# Laser_Control_Board.net
KiCad netlist of a schematic drawn in EAGLE
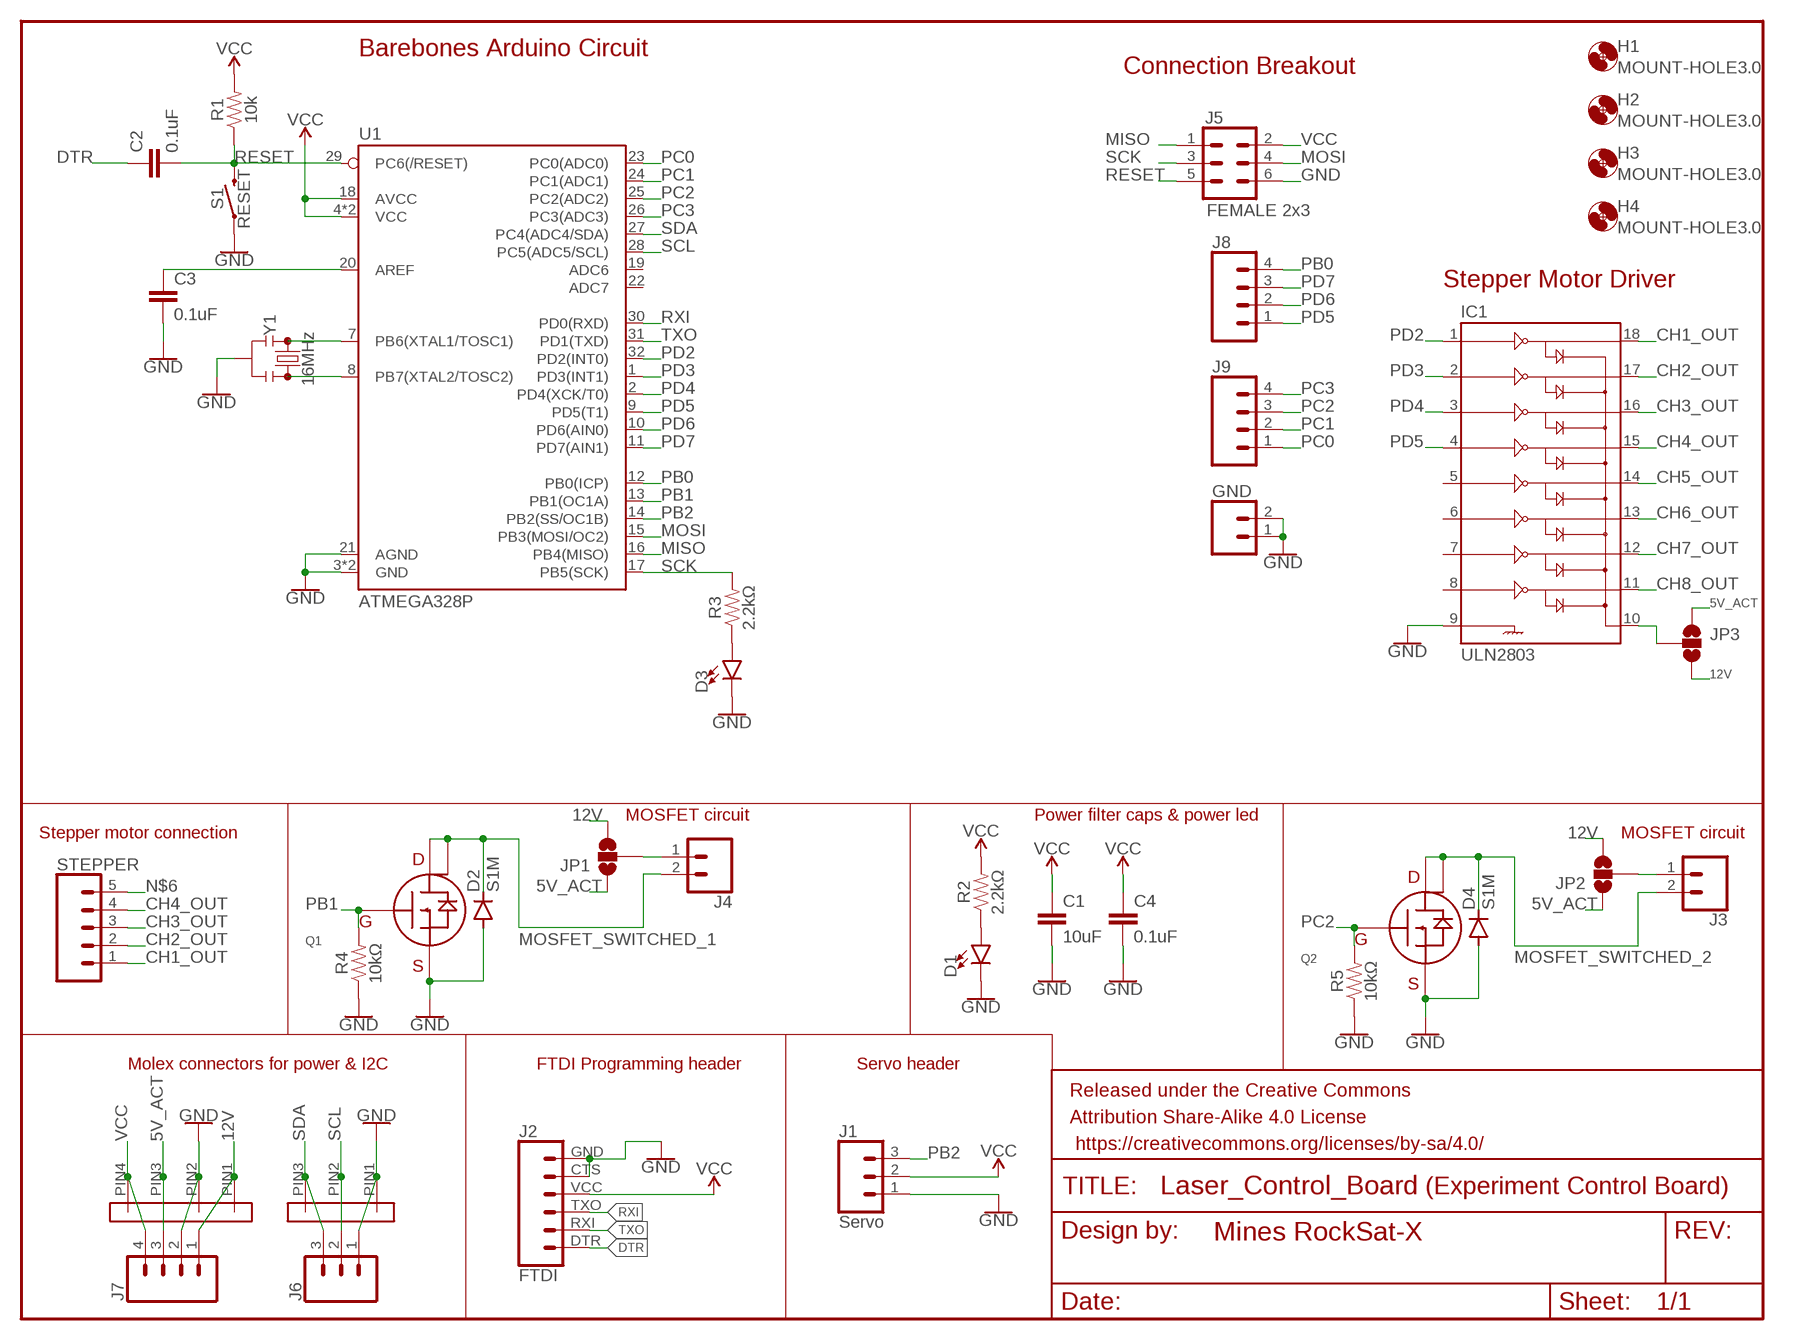
[diagram p0: schematic, sheet 1]

(export (version "E")
  (design (tool "Eeschema 10.0.6"))
  (components
    (comp (ref "C1")
      (value "10uF")
      (footprint "eagle-import:0805")
      (libsource (lib "eagle-import") (part "10UF-0805-10V-10%"))
    )
    (comp (ref "C2")
      (value "0.1uF")
      (footprint "eagle-import:0805")
      (libsource (lib "eagle-import") (part "2.2UF-0805-25V-(+80/-20%)"))
    )
    (comp (ref "C3")
      (value "0.1uF")
      (footprint "eagle-import:0805")
      (libsource (lib "eagle-import") (part "2.2UF-0805-25V-(+80/-20%)"))
    )
    (comp (ref "C4")
      (value "0.1uF")
      (footprint "eagle-import:0805")
      (libsource (lib "eagle-import") (part "2.2UF-0805-25V-(+80/-20%)"))
    )
    (comp (ref "D1")
      (value "LED-GREEN1206")
      (footprint "eagle-import:LED-1206")
      (libsource (lib "eagle-import") (part "LED-GREEN1206"))
    )
    (comp (ref "D2")
      (value "S1M")
      (footprint "eagle-import:SMA")
      (libsource (lib "eagle-import") (part "S1M"))
    )
    (comp (ref "D3")
      (value "LED-GREEN1206")
      (footprint "eagle-import:LED-1206")
      (libsource (lib "eagle-import") (part "LED-GREEN1206"))
    )
    (comp (ref "D4")
      (value "S1M")
      (footprint "eagle-import:SMA")
      (libsource (lib "eagle-import") (part "S1M"))
    )
    (comp (ref "FRAME1")
      (value "FRAME-LETTERNO_PACKAGE")
      (footprint "eagle-import:DUMMY")
      (fields
        (field (name "DESIGNER") "Mines RockSat-X")
        (field (name "VERSION") "1")
        (field (name "DESIGNER_1") "Mines RockSat-X")
      )
      (libsource (lib "eagle-import") (part "FRAME-LETTERNO_PACKAGE"))
    )
    (comp (ref "GND")
      (value "CONN_02LOCK_LONGPADS")
      (footprint "eagle-import:1X02_LOCK_LONGPADS")
      (libsource (lib "eagle-import") (part "CONN_02LOCK_LONGPADS"))
    )
    (comp (ref "H1")
      (value "MOUNT-HOLE3.0")
      (footprint "eagle-import:3,0")
      (libsource (lib "eagle-import") (part "MOUNT-HOLE3.0"))
    )
    (comp (ref "H2")
      (value "MOUNT-HOLE3.0")
      (footprint "eagle-import:3,0")
      (libsource (lib "eagle-import") (part "MOUNT-HOLE3.0"))
    )
    (comp (ref "H3")
      (value "MOUNT-HOLE3.0")
      (footprint "eagle-import:3,0")
      (libsource (lib "eagle-import") (part "MOUNT-HOLE3.0"))
    )
    (comp (ref "H4")
      (value "MOUNT-HOLE3.0")
      (footprint "eagle-import:3,0")
      (libsource (lib "eagle-import") (part "MOUNT-HOLE3.0"))
    )
    (comp (ref "IC1")
      (value "ULN2803")
      (footprint "eagle-import:SO18L")
      (libsource (lib "eagle-import") (part "ULN2803SOICW"))
    )
    (comp (ref "J1")
      (value "Servo")
      (footprint "eagle-import:1X03")
      (libsource (lib "eagle-import") (part "CONN_03"))
    )
    (comp (ref "J2")
      (value "FTDI")
      (footprint "eagle-import:FTDI_BASIC")
      (libsource (lib "eagle-import") (part "6_PIN_SERIAL_CABLEPTH"))
    )
    (comp (ref "J3")
      (value "CONN_02")
      (footprint "eagle-import:1X02")
      (libsource (lib "eagle-import") (part "CONN_02"))
    )
    (comp (ref "J4")
      (value "CONN_02")
      (footprint "eagle-import:1X02")
      (libsource (lib "eagle-import") (part "CONN_02"))
    )
    (comp (ref "J5")
      (value "FEMALE 2x3")
      (footprint "eagle-import:2X3")
      (libsource (lib "eagle-import") (part "CONN_03X2FEMALE"))
    )
    (comp (ref "J6")
      (value "CONN_03")
      (footprint "eagle-import:1X03")
      (libsource (lib "eagle-import") (part "CONN_03"))
    )
    (comp (ref "J7")
      (value "CONN_04LOCK")
      (footprint "eagle-import:1X04_LOCK")
      (libsource (lib "eagle-import") (part "CONN_04LOCK"))
    )
    (comp (ref "J8")
      (value "CONN_04LOCK")
      (footprint "eagle-import:1X04_LOCK")
      (libsource (lib "eagle-import") (part "CONN_04LOCK"))
    )
    (comp (ref "J9")
      (value "CONN_04LOCK")
      (footprint "eagle-import:1X04_LOCK")
      (libsource (lib "eagle-import") (part "CONN_04LOCK"))
    )
    (comp (ref "JP1")
      (value "JUMPER-SMT_3_NO_NO_SILK")
      (footprint "eagle-import:SMT-JUMPER_3_0-NO_TRACE_NO-SILK")
      (libsource (lib "eagle-import") (part "JUMPER-SMT_3_NO_NO_SILK"))
    )
    (comp (ref "JP2")
      (value "JUMPER-SMT_3_NO_NO_SILK")
      (footprint "eagle-import:SMT-JUMPER_3_0-NO_TRACE_NO-SILK")
      (libsource (lib "eagle-import") (part "JUMPER-SMT_3_NO_NO_SILK"))
    )
    (comp (ref "JP3")
      (value "JUMPER-SMT_3_NO_NO_SILK")
      (footprint "eagle-import:SMT-JUMPER_3_0-NO_TRACE_NO-SILK")
      (libsource (lib "eagle-import") (part "JUMPER-SMT_3_NO_NO_SILK"))
    )
    (comp (ref "Q1")
      (value "BUK9880-55A")
      (footprint "eagle-import:SOT223")
      (libsource (lib "eagle-import") (part "BUK9880-55A"))
    )
    (comp (ref "Q2")
      (value "BUK9880-55A")
      (footprint "eagle-import:SOT223")
      (libsource (lib "eagle-import") (part "BUK9880-55A"))
    )
    (comp (ref "R1")
      (value "10k")
      (footprint "eagle-import:0805")
      (libsource (lib "eagle-import") (part "RESISTOR0805"))
    )
    (comp (ref "R2")
      (value "2.2kΩ")
      (footprint "eagle-import:0805")
      (libsource (lib "eagle-import") (part "RESISTOR0805"))
    )
    (comp (ref "R3")
      (value "2.2kΩ")
      (footprint "eagle-import:0805")
      (libsource (lib "eagle-import") (part "RESISTOR0805"))
    )
    (comp (ref "R4")
      (value "10kΩ")
      (footprint "eagle-import:0805")
      (libsource (lib "eagle-import") (part "RESISTOR0805"))
    )
    (comp (ref "R5")
      (value "10kΩ")
      (footprint "eagle-import:0805")
      (libsource (lib "eagle-import") (part "RESISTOR0805"))
    )
    (comp (ref "S1")
      (value "RESET")
      (footprint "eagle-import:TACTILE_SWITCH_SMD_5.2MM")
      (libsource (lib "eagle-import") (part "MOMENTARY-SWITCH-SPST-SMD-5.2-REDUNDANT"))
    )
    (comp (ref "STEPPER")
      (value "CONN_05")
      (footprint "eagle-import:1X05")
      (libsource (lib "eagle-import") (part "CONN_05"))
    )
    (comp (ref "U$1")
      (value "MOLEX_4PIN")
      (footprint "eagle-import:MOLEX_4PIN")
      (libsource (lib "eagle-import") (part "MOLEX_4PIN"))
    )
    (comp (ref "U$2")
      (value "MOLEX_3PIN")
      (footprint "eagle-import:MOLEX_3PIN")
      (libsource (lib "eagle-import") (part "MOLEX_3PIN"))
    )
    (comp (ref "U1")
      (value "ATMEGA328P")
      (footprint "eagle-import:TQFP32-08")
      (libsource (lib "eagle-import") (part "ATMEGA328P_TQFP"))
    )
    (comp (ref "Y1")
      (value "16MHz")
      (footprint "eagle-import:RESONATOR-SMD-3.2X1.3")
      (libsource (lib "eagle-import") (part "RESONATOR-16MHZSMD_3.2X1.3"))
    )
  )
  (nets
    (net (code "1") (name "/5V_ACT") (class "Default")
      (node (ref "J7") (pin "3") (pinfunction "3_3") (pintype "passive"))
      (node (ref "JP1") (pin "1") (pinfunction "1_1") (pintype "passive"))
      (node (ref "JP2") (pin "1") (pinfunction "1_1") (pintype "passive"))
      (node (ref "JP3") (pin "1") (pinfunction "1_1") (pintype "passive"))
      (node (ref "U$1") (pin "PIN3") (pinfunction "PIN3_PIN3") (pintype "bidirectional"))
    )
    (net (code "2") (name "/12V") (class "Default")
      (node (ref "J7") (pin "1") (pinfunction "1_1") (pintype "passive"))
      (node (ref "JP1") (pin "3") (pinfunction "3_3") (pintype "passive"))
      (node (ref "JP2") (pin "3") (pinfunction "3_3") (pintype "passive"))
      (node (ref "JP3") (pin "3") (pinfunction "3_3") (pintype "passive"))
      (node (ref "U$1") (pin "PIN1") (pinfunction "PIN1_PIN1") (pintype "bidirectional"))
    )
    (net (code "3") (name "/CH1_OUT") (class "Default")
      (node (ref "IC1") (pin "18") (pinfunction "18_18") (pintype "bidirectional"))
      (node (ref "STEPPER") (pin "1") (pinfunction "1_1") (pintype "passive"))
    )
    (net (code "4") (name "/CH2_OUT") (class "Default")
      (node (ref "IC1") (pin "17") (pinfunction "17_17") (pintype "bidirectional"))
      (node (ref "STEPPER") (pin "2") (pinfunction "2_2") (pintype "passive"))
    )
    (net (code "5") (name "/CH3_OUT") (class "Default")
      (node (ref "IC1") (pin "16") (pinfunction "16_16") (pintype "bidirectional"))
      (node (ref "STEPPER") (pin "3") (pinfunction "3_3") (pintype "passive"))
    )
    (net (code "6") (name "/CH4_OUT") (class "Default")
      (node (ref "IC1") (pin "15") (pinfunction "15_15") (pintype "bidirectional"))
      (node (ref "STEPPER") (pin "4") (pinfunction "4_4") (pintype "passive"))
    )
    (net (code "7") (name "/CH5_OUT") (class "Default")
      (node (ref "IC1") (pin "14") (pinfunction "14_14") (pintype "bidirectional"))
    )
    (net (code "8") (name "/CH6_OUT") (class "Default")
      (node (ref "IC1") (pin "13") (pinfunction "13_13") (pintype "bidirectional"))
    )
    (net (code "9") (name "/CH7_OUT") (class "Default")
      (node (ref "IC1") (pin "12") (pinfunction "12_12") (pintype "bidirectional"))
    )
    (net (code "10") (name "/CH8_OUT") (class "Default")
      (node (ref "IC1") (pin "11") (pinfunction "11_11") (pintype "bidirectional"))
    )
    (net (code "11") (name "/MISO") (class "Default")
      (node (ref "J5") (pin "1") (pinfunction "1_1") (pintype "bidirectional"))
      (node (ref "U1") (pin "16") (pinfunction "PB4(MISO)_16") (pintype "bidirectional"))
    )
    (net (code "12") (name "/MOSFET_SWITCHED_1") (class "Default")
      (node (ref "D2") (pin "C") (pinfunction "C_C") (pintype "passive"))
      (node (ref "J4") (pin "2") (pinfunction "2_2") (pintype "passive"))
      (node (ref "Q1") (pin "2") (pinfunction "DRAIN_2") (pintype "bidirectional"))
      (node (ref "Q1") (pin "4") (pinfunction "DRAIN_TAB_4") (pintype "bidirectional"))
    )
    (net (code "13") (name "/MOSFET_SWITCHED_2") (class "Default")
      (node (ref "D4") (pin "C") (pinfunction "C_C") (pintype "passive"))
      (node (ref "J3") (pin "2") (pinfunction "2_2") (pintype "passive"))
      (node (ref "Q2") (pin "2") (pinfunction "DRAIN_2") (pintype "bidirectional"))
      (node (ref "Q2") (pin "4") (pinfunction "DRAIN_TAB_4") (pintype "bidirectional"))
    )
    (net (code "14") (name "/MOSI") (class "Default")
      (node (ref "J5") (pin "4") (pinfunction "4_4") (pintype "bidirectional"))
      (node (ref "U1") (pin "15") (pinfunction "PB3(MOSI/OC2)_15") (pintype "bidirectional"))
    )
    (net (code "15") (name "/N$6") (class "Default")
      (node (ref "IC1") (pin "10") (pinfunction "10_10") (pintype "bidirectional"))
      (node (ref "JP3") (pin "2") (pinfunction "2_2") (pintype "passive"))
      (node (ref "STEPPER") (pin "5") (pinfunction "5_5") (pintype "passive"))
    )
    (net (code "16") (name "/PB0") (class "Default")
      (node (ref "J8") (pin "4") (pinfunction "4_4") (pintype "passive"))
      (node (ref "U1") (pin "12") (pinfunction "PB0(ICP)_12") (pintype "bidirectional"))
    )
    (net (code "17") (name "/PB1") (class "Default")
      (node (ref "Q1") (pin "1") (pinfunction "GATE_1") (pintype "bidirectional"))
      (node (ref "R4") (pin "2") (pinfunction "2_2") (pintype "passive"))
      (node (ref "U1") (pin "13") (pinfunction "PB1(OC1A)_13") (pintype "bidirectional"))
    )
    (net (code "18") (name "/PB2") (class "Default")
      (node (ref "J1") (pin "3") (pinfunction "3_3") (pintype "passive"))
      (node (ref "U1") (pin "14") (pinfunction "PB2(SS/OC1B)_14") (pintype "bidirectional"))
    )
    (net (code "19") (name "/PC0") (class "Default")
      (node (ref "J9") (pin "1") (pinfunction "1_1") (pintype "passive"))
      (node (ref "U1") (pin "23") (pinfunction "PC0(ADC0)_23") (pintype "bidirectional"))
    )
    (net (code "20") (name "/PC1") (class "Default")
      (node (ref "J9") (pin "2") (pinfunction "2_2") (pintype "passive"))
      (node (ref "U1") (pin "24") (pinfunction "PC1(ADC1)_24") (pintype "bidirectional"))
    )
    (net (code "21") (name "/PC2") (class "Default")
      (node (ref "J9") (pin "3") (pinfunction "3_3") (pintype "passive"))
      (node (ref "Q2") (pin "1") (pinfunction "GATE_1") (pintype "bidirectional"))
      (node (ref "R5") (pin "2") (pinfunction "2_2") (pintype "passive"))
      (node (ref "U1") (pin "25") (pinfunction "PC2(ADC2)_25") (pintype "bidirectional"))
    )
    (net (code "22") (name "/PC3") (class "Default")
      (node (ref "J9") (pin "4") (pinfunction "4_4") (pintype "passive"))
      (node (ref "U1") (pin "26") (pinfunction "PC3(ADC3)_26") (pintype "bidirectional"))
    )
    (net (code "23") (name "/PD2") (class "Default")
      (node (ref "IC1") (pin "1") (pinfunction "1_1") (pintype "bidirectional"))
      (node (ref "U1") (pin "32") (pinfunction "PD2(INT0)_32") (pintype "bidirectional"))
    )
    (net (code "24") (name "/PD3") (class "Default")
      (node (ref "IC1") (pin "2") (pinfunction "2_2") (pintype "bidirectional"))
      (node (ref "U1") (pin "1") (pinfunction "PD3(INT1)_1") (pintype "bidirectional"))
    )
    (net (code "25") (name "/PD4") (class "Default")
      (node (ref "IC1") (pin "3") (pinfunction "3_3") (pintype "bidirectional"))
      (node (ref "U1") (pin "2") (pinfunction "PD4(XCK/T0)_2") (pintype "bidirectional"))
    )
    (net (code "26") (name "/PD5") (class "Default")
      (node (ref "IC1") (pin "4") (pinfunction "4_4") (pintype "bidirectional"))
      (node (ref "J8") (pin "1") (pinfunction "1_1") (pintype "passive"))
      (node (ref "U1") (pin "9") (pinfunction "PD5(T1)_9") (pintype "bidirectional"))
    )
    (net (code "27") (name "/PD6") (class "Default")
      (node (ref "J8") (pin "2") (pinfunction "2_2") (pintype "passive"))
      (node (ref "U1") (pin "10") (pinfunction "PD6(AIN0)_10") (pintype "bidirectional"))
    )
    (net (code "28") (name "/PD7") (class "Default")
      (node (ref "J8") (pin "3") (pinfunction "3_3") (pintype "passive"))
      (node (ref "U1") (pin "11") (pinfunction "PD7(AIN1)_11") (pintype "bidirectional"))
    )
    (net (code "29") (name "/RESET") (class "Default")
      (node (ref "C2") (pin "2") (pinfunction "2_2") (pintype "passive"))
      (node (ref "J5") (pin "5") (pinfunction "5_5") (pintype "bidirectional"))
      (node (ref "R1") (pin "1") (pinfunction "1_1") (pintype "passive"))
      (node (ref "S1") (pin "3") (pinfunction "2_3") (pintype "passive"))
      (node (ref "S1") (pin "4") (pinfunction "2_4") (pintype "passive"))
      (node (ref "U1") (pin "29") (pinfunction "PC6(/RESET)_29") (pintype "bidirectional"))
    )
    (net (code "30") (name "/SCK") (class "Default")
      (node (ref "J5") (pin "3") (pinfunction "3_3") (pintype "bidirectional"))
      (node (ref "R3") (pin "2") (pinfunction "2_2") (pintype "passive"))
      (node (ref "U1") (pin "17") (pinfunction "PB5(SCK)_17") (pintype "bidirectional"))
    )
    (net (code "31") (name "/SCL") (class "Default")
      (node (ref "J6") (pin "2") (pinfunction "2_2") (pintype "passive"))
      (node (ref "U$2") (pin "PIN2") (pinfunction "PIN2_PIN2") (pintype "bidirectional"))
      (node (ref "U1") (pin "28") (pinfunction "PC5(ADC5/SCL)_28") (pintype "bidirectional"))
    )
    (net (code "32") (name "/SDA") (class "Default")
      (node (ref "J6") (pin "3") (pinfunction "3_3") (pintype "passive"))
      (node (ref "U$2") (pin "PIN3") (pinfunction "PIN3_PIN3") (pintype "bidirectional"))
      (node (ref "U1") (pin "27") (pinfunction "PC4(ADC4/SDA)_27") (pintype "bidirectional"))
    )
    (net (code "33") (name "DTR") (class "Default")
      (node (ref "C2") (pin "1") (pinfunction "1_1") (pintype "passive"))
      (node (ref "J2") (pin "DTR") (pinfunction "1_DTR") (pintype "passive"))
    )
    (net (code "34") (name "GND") (class "Default")
      (node (ref "C1") (pin "2") (pinfunction "2_2") (pintype "passive"))
      (node (ref "C3") (pin "2") (pinfunction "2_2") (pintype "passive"))
      (node (ref "C4") (pin "2") (pinfunction "2_2") (pintype "passive"))
      (node (ref "D1") (pin "C") (pinfunction "C_C") (pintype "passive"))
      (node (ref "D2") (pin "A") (pinfunction "A_A") (pintype "passive"))
      (node (ref "D3") (pin "C") (pinfunction "C_C") (pintype "passive"))
      (node (ref "D4") (pin "A") (pinfunction "A_A") (pintype "passive"))
      (node (ref "GND") (pin "1") (pinfunction "1_1") (pintype "passive"))
      (node (ref "GND") (pin "2") (pinfunction "2_2") (pintype "passive"))
      (node (ref "IC1") (pin "9") (pinfunction "9_9") (pintype "bidirectional"))
      (node (ref "J1") (pin "1") (pinfunction "1_1") (pintype "passive"))
      (node (ref "J2") (pin "CTS") (pinfunction "5_CTS") (pintype "passive"))
      (node (ref "J2") (pin "GND") (pinfunction "6_GND") (pintype "passive"))
      (node (ref "J5") (pin "6") (pinfunction "6_6") (pintype "bidirectional"))
      (node (ref "J6") (pin "1") (pinfunction "1_1") (pintype "passive"))
      (node (ref "J7") (pin "2") (pinfunction "2_2") (pintype "passive"))
      (node (ref "Q1") (pin "3") (pinfunction "SOURCE_3") (pintype "bidirectional"))
      (node (ref "Q2") (pin "3") (pinfunction "SOURCE_3") (pintype "bidirectional"))
      (node (ref "R4") (pin "1") (pinfunction "1_1") (pintype "passive"))
      (node (ref "R5") (pin "1") (pinfunction "1_1") (pintype "passive"))
      (node (ref "S1") (pin "1") (pinfunction "1_1") (pintype "passive"))
      (node (ref "S1") (pin "2") (pinfunction "1_2") (pintype "passive"))
      (node (ref "U$1") (pin "PIN2") (pinfunction "PIN2_PIN2") (pintype "bidirectional"))
      (node (ref "U$2") (pin "PIN1") (pinfunction "PIN1_PIN1") (pintype "bidirectional"))
      (node (ref "U1") (pin "21") (pinfunction "AGND_21") (pintype "bidirectional"))
      (node (ref "U1") (pin "3") (pinfunction "GND_3") (pintype "bidirectional"))
      (node (ref "U1") (pin "5") (pinfunction "GND_5") (pintype "bidirectional"))
      (node (ref "Y1") (pin "2") (pinfunction "2_2") (pintype "passive"))
    )
    (net (code "35") (name "Net-(D1-PadA)") (class "Default")
      (node (ref "D1") (pin "A") (pinfunction "A_A") (pintype "passive"))
      (node (ref "R2") (pin "1") (pinfunction "1_1") (pintype "passive"))
    )
    (net (code "36") (name "Net-(D3-PadA)") (class "Default")
      (node (ref "D3") (pin "A") (pinfunction "A_A") (pintype "passive"))
      (node (ref "R3") (pin "1") (pinfunction "1_1") (pintype "passive"))
    )
    (net (code "37") (name "Net-(J3-Pad1)") (class "Default")
      (node (ref "J3") (pin "1") (pinfunction "1_1") (pintype "passive"))
      (node (ref "JP2") (pin "2") (pinfunction "2_2") (pintype "passive"))
    )
    (net (code "38") (name "Net-(J4-Pad1)") (class "Default")
      (node (ref "J4") (pin "1") (pinfunction "1_1") (pintype "passive"))
      (node (ref "JP1") (pin "2") (pinfunction "2_2") (pintype "passive"))
    )
    (net (code "39") (name "Net-(U1-AREF)") (class "Default")
      (node (ref "C3") (pin "1") (pinfunction "1_1") (pintype "passive"))
      (node (ref "U1") (pin "20") (pinfunction "AREF_20") (pintype "bidirectional"))
    )
    (net (code "40") (name "Net-(U1-PB6(XTAL1{slash}TOSC1))") (class "Default")
      (node (ref "U1") (pin "7") (pinfunction "PB6(XTAL1/TOSC1)_7") (pintype "bidirectional"))
      (node (ref "Y1") (pin "1") (pinfunction "1_1") (pintype "passive"))
    )
    (net (code "41") (name "Net-(U1-PB7(XTAL2{slash}TOSC2))") (class "Default")
      (node (ref "U1") (pin "8") (pinfunction "PB7(XTAL2/TOSC2)_8") (pintype "bidirectional"))
      (node (ref "Y1") (pin "3") (pinfunction "3_3") (pintype "passive"))
    )
    (net (code "42") (name "RXI") (class "Default")
      (node (ref "J2") (pin "TXO") (pinfunction "3_TXO") (pintype "passive"))
      (node (ref "U1") (pin "30") (pinfunction "PD0(RXD)_30") (pintype "bidirectional"))
    )
    (net (code "43") (name "TXO") (class "Default")
      (node (ref "J2") (pin "RXI") (pinfunction "2_RXI") (pintype "passive"))
      (node (ref "U1") (pin "31") (pinfunction "PD1(TXD)_31") (pintype "bidirectional"))
    )
    (net (code "44") (name "VCC") (class "Default")
      (node (ref "C1") (pin "1") (pinfunction "1_1") (pintype "passive"))
      (node (ref "C4") (pin "1") (pinfunction "1_1") (pintype "passive"))
      (node (ref "J1") (pin "2") (pinfunction "2_2") (pintype "passive"))
      (node (ref "J2") (pin "VCC") (pinfunction "4_VCC") (pintype "passive"))
      (node (ref "J5") (pin "2") (pinfunction "2_2") (pintype "bidirectional"))
      (node (ref "J7") (pin "4") (pinfunction "4_4") (pintype "passive"))
      (node (ref "R1") (pin "2") (pinfunction "2_2") (pintype "passive"))
      (node (ref "R2") (pin "2") (pinfunction "2_2") (pintype "passive"))
      (node (ref "U$1") (pin "PIN4") (pinfunction "PIN4_PIN4") (pintype "bidirectional"))
      (node (ref "U1") (pin "18") (pinfunction "AVCC_18") (pintype "bidirectional"))
      (node (ref "U1") (pin "4") (pinfunction "VCC_4") (pintype "bidirectional"))
      (node (ref "U1") (pin "6") (pinfunction "VCC_6") (pintype "bidirectional"))
    )
    (net (code "45") (name "unconnected-(IC1-Pad5)") (class "Default")
      (node (ref "IC1") (pin "5") (pinfunction "5_5") (pintype "bidirectional"))
    )
    (net (code "46") (name "unconnected-(IC1-Pad6)") (class "Default")
      (node (ref "IC1") (pin "6") (pinfunction "6_6") (pintype "bidirectional"))
    )
    (net (code "47") (name "unconnected-(IC1-Pad7)") (class "Default")
      (node (ref "IC1") (pin "7") (pinfunction "7_7") (pintype "bidirectional"))
    )
    (net (code "48") (name "unconnected-(IC1-Pad8)") (class "Default")
      (node (ref "IC1") (pin "8") (pinfunction "8_8") (pintype "bidirectional"))
    )
    (net (code "49") (name "unconnected-(U1-ADC6-Pad19)") (class "Default")
      (node (ref "U1") (pin "19") (pinfunction "ADC6_19") (pintype "bidirectional"))
    )
    (net (code "50") (name "unconnected-(U1-ADC7-Pad22)") (class "Default")
      (node (ref "U1") (pin "22") (pinfunction "ADC7_22") (pintype "bidirectional"))
    )
  )
)
